# TMotor_Rev0.net
KiCad netlist of a schematic drawn in EAGLE
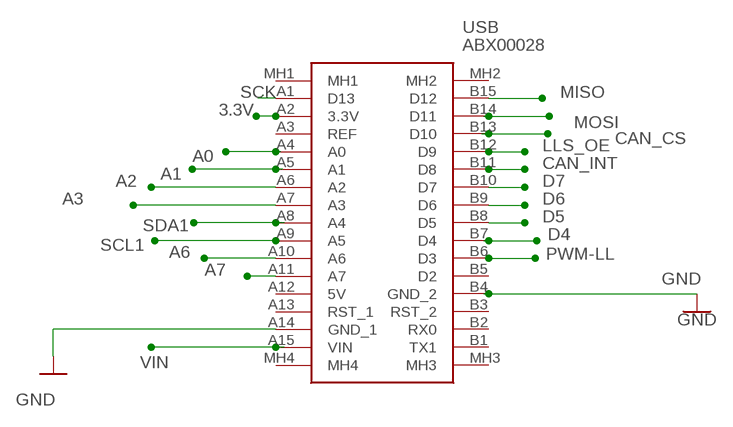
[diagram p0: schematic, sheet 1]
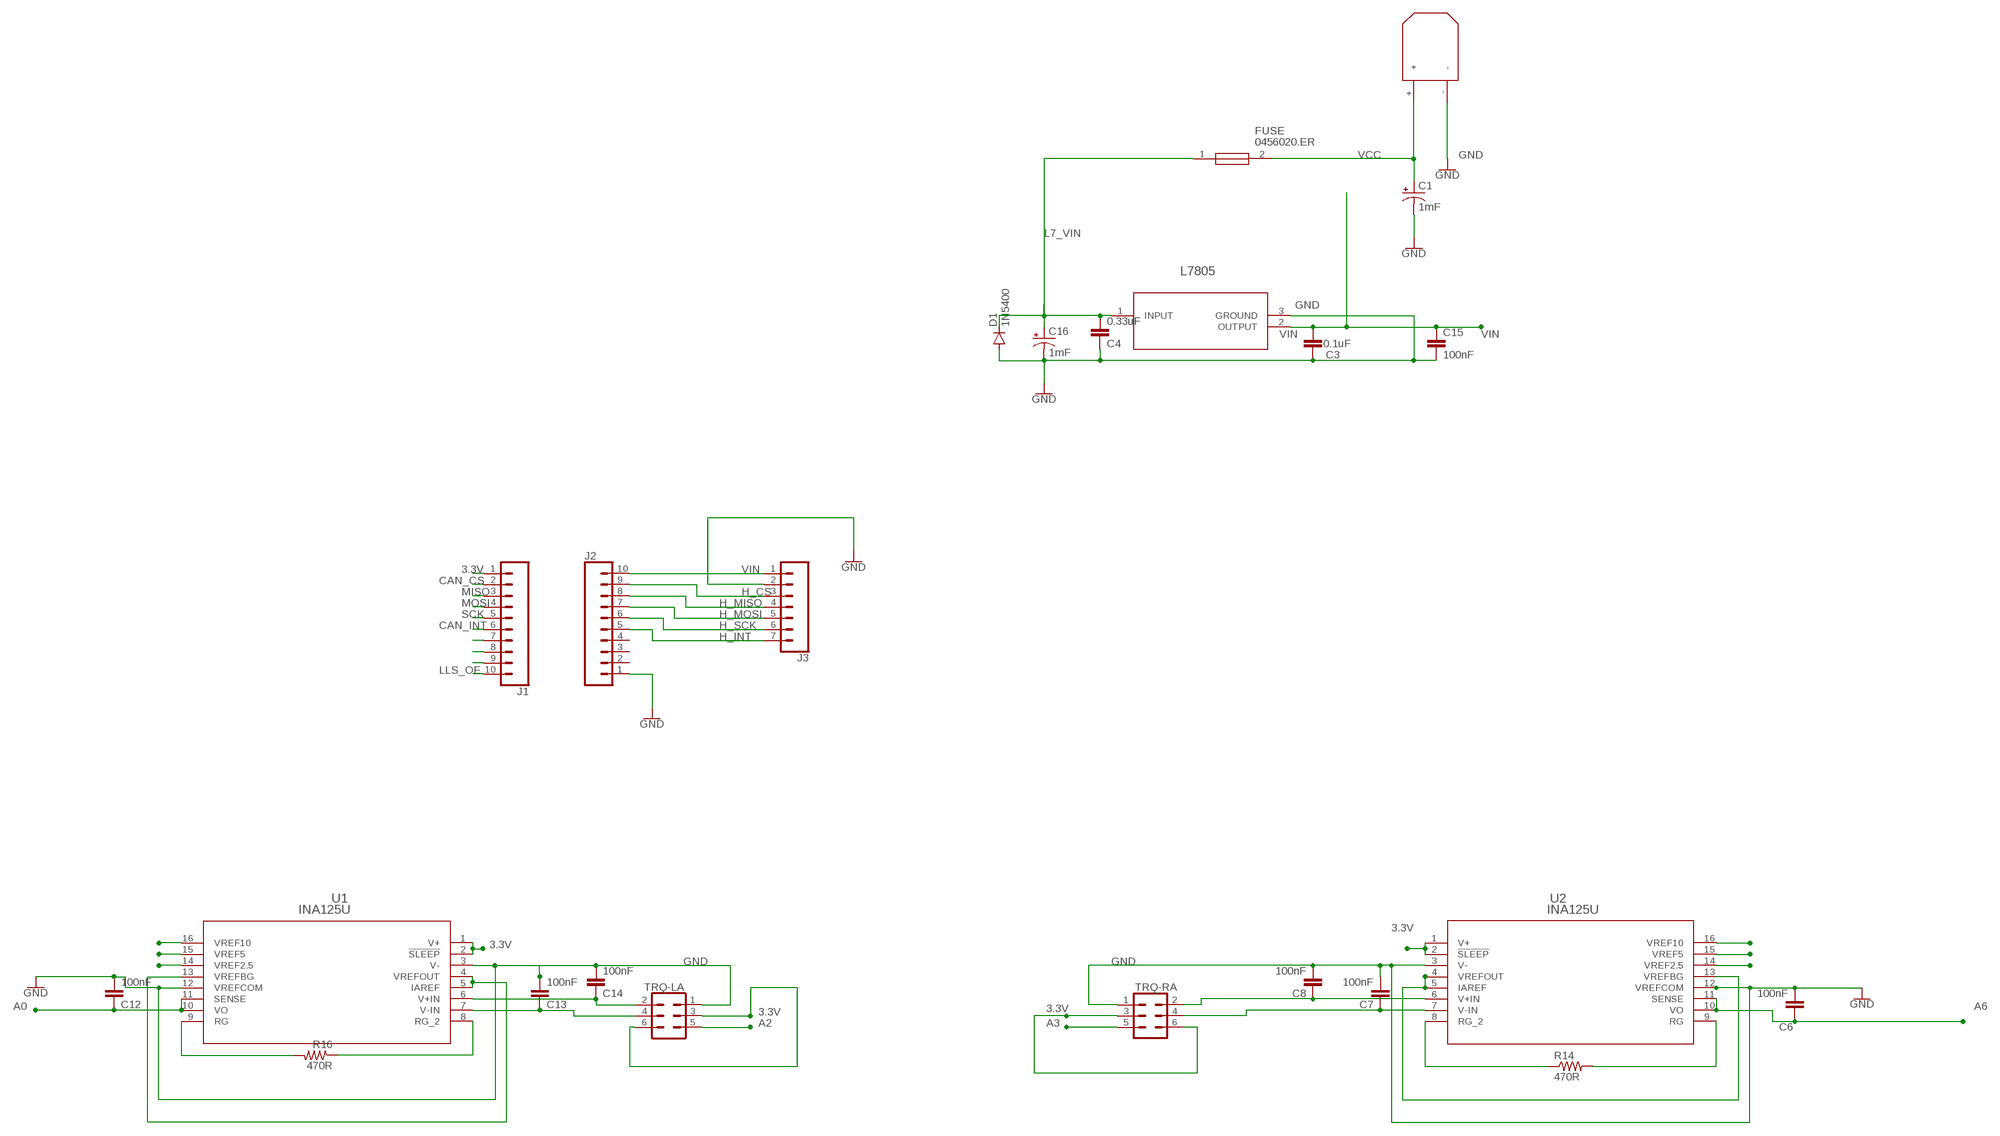
[diagram p1: schematic, sheet 2]
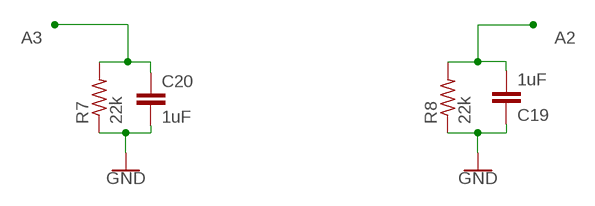
[diagram p2: schematic, sheet 3]

(export (version "E")
  (design (tool "Eeschema 10.0.6"))
  (components
    (comp (ref "C19")
      (value "1uF")
      (footprint "eagle-import:C050-024X044")
      (libsource (lib "eagle-import") (part "C-EU050-024X044"))
    )
    (comp (ref "C20")
      (value "1uF")
      (footprint "eagle-import:C050-024X044")
      (libsource (lib "eagle-import") (part "C-EU050-024X044"))
    )
    (comp (ref "R7")
      (value "22k")
      (footprint "eagle-import:0207_10")
      (libsource (lib "eagle-import") (part "resistor_348_R-US_0207/10"))
    )
    (comp (ref "R8")
      (value "22k")
      (footprint "eagle-import:0207_10")
      (libsource (lib "eagle-import") (part "resistor_348_R-US_0207/10"))
    )
    (comp (ref "C1")
      (value "1mF")
      (footprint "eagle-import:E5-10,5")
      (libsource (lib "eagle-import") (part "CPOL-USE5-10.5"))
    )
    (comp (ref "C3")
      (value "0.1uF")
      (footprint "eagle-import:C050-024X044")
      (libsource (lib "eagle-import") (part "C-EU050-024X044"))
    )
    (comp (ref "C4")
      (value "0.33uF")
      (footprint "eagle-import:C050-024X044")
      (libsource (lib "eagle-import") (part "C-EU050-024X044"))
    )
    (comp (ref "C6")
      (value "100nF")
      (footprint "eagle-import:C050-024X044")
      (libsource (lib "eagle-import") (part "C-EU050-024X044"))
    )
    (comp (ref "C7")
      (value "100nF")
      (footprint "eagle-import:C050-024X044")
      (libsource (lib "eagle-import") (part "C-EU050-024X044"))
    )
    (comp (ref "C8")
      (value "100nF")
      (footprint "eagle-import:C050-024X044")
      (libsource (lib "eagle-import") (part "C-EU050-024X044"))
    )
    (comp (ref "C12")
      (value "100nF")
      (footprint "eagle-import:C050-024X044")
      (libsource (lib "eagle-import") (part "C-EU050-024X044"))
    )
    (comp (ref "C13")
      (value "100nF")
      (footprint "eagle-import:C050-024X044")
      (libsource (lib "eagle-import") (part "C-EU050-024X044"))
    )
    (comp (ref "C14")
      (value "100nF")
      (footprint "eagle-import:C050-024X044")
      (libsource (lib "eagle-import") (part "C-EU050-024X044"))
    )
    (comp (ref "C15")
      (value "100nF")
      (footprint "eagle-import:C050-024X044")
      (libsource (lib "eagle-import") (part "C-EU050-024X044"))
    )
    (comp (ref "C16")
      (value "1mF")
      (footprint "eagle-import:E5-10,5")
      (libsource (lib "eagle-import") (part "CPOL-USE5-10.5"))
    )
    (comp (ref "D1")
      (value "1N5400")
      (footprint "eagle-import:DO201-15")
      (libsource (lib "eagle-import") (part "1N5400"))
    )
    (comp (ref "FUSE")
      (value "0456020.ER")
      (footprint "eagle-import:FUSC10131X312N")
      (fields (field (name "MOUSER_PART_NUMBER") "576-0456020.ER"))
      (libsource (lib "eagle-import") (part "0456020.ER"))
    )
    (comp (ref "J1")
      (value "CONN_10\"")
      (footprint "eagle-import:1X10")
      (libsource (lib "eagle-import") (part "CONN_10{dblquote}"))
    )
    (comp (ref "J2")
      (value "CONN_10\"")
      (footprint "eagle-import:1X10")
      (libsource (lib "eagle-import") (part "CONN_10{dblquote}"))
    )
    (comp (ref "J3")
      (value "CONN_07")
      (footprint "eagle-import:1X07")
      (libsource (lib "eagle-import") (part "CONN_07"))
    )
    (comp (ref "L7805")
      (value "L7805CDT-TR")
      (footprint "eagle-import:DPAK_STM")
      (libsource (lib "eagle-import") (part "L7805CDT-TR"))
    )
    (comp (ref "R14")
      (value "470R")
      (footprint "eagle-import:0207_10")
      (libsource (lib "eagle-import") (part "R-US_0207/10"))
    )
    (comp (ref "R16")
      (value "470R")
      (footprint "eagle-import:0207_10")
      (libsource (lib "eagle-import") (part "R-US_0207/10"))
    )
    (comp (ref "TRQ-LA")
      (value "CONN_03X2SHROUD")
      (footprint "eagle-import:2X3-SHROUDED")
      (libsource (lib "eagle-import") (part "CONN_03X2SHROUD"))
    )
    (comp (ref "TRQ-RA")
      (value "CONN_03X2SHROUD")
      (footprint "eagle-import:2X3-SHROUDED")
      (libsource (lib "eagle-import") (part "CONN_03X2SHROUD"))
    )
    (comp (ref "U$9")
      (value "XT30")
      (footprint "eagle-import:XT30_HORIZONTAL")
      (libsource (lib "eagle-import") (part "XT30"))
    )
    (comp (ref "U1")
      (value "INA125U")
      (footprint "eagle-import:D16")
      (fields (field (name "GENERIC_PART_NUMBER") "INA125") (field (name "MANUFACTURER") "Texas Instruments"))
      (libsource (lib "eagle-import") (part "INA125U"))
    )
    (comp (ref "U2")
      (value "INA125U")
      (footprint "eagle-import:D16")
      (fields (field (name "GENERIC_PART_NUMBER") "INA125") (field (name "MANUFACTURER") "Texas Instruments"))
      (libsource (lib "eagle-import") (part "INA125U"))
    )
    (comp (ref "USB")
      (value "ABX00028")
      (footprint "eagle-import:ABX00028")
      (fields (field (name "MOUSER_PART_NUMBER") "782-ABX00028"))
      (libsource (lib "eagle-import") (part "ABX00028"))
    )
  )
  (nets
    (net (code "1") (name "3.3V") (class "Default")
      (node (ref "J1") (pin "1") (pinfunction "1_1") (pintype "passive"))
      (node (ref "TRQ-LA") (pin "3") (pinfunction "3_3") (pintype "bidirectional"))
      (node (ref "TRQ-LA") (pin "6") (pinfunction "6_6") (pintype "bidirectional"))
      (node (ref "TRQ-RA") (pin "3") (pinfunction "3_3") (pintype "bidirectional"))
      (node (ref "TRQ-RA") (pin "6") (pinfunction "6_6") (pintype "bidirectional"))
      (node (ref "U1") (pin "1") (pinfunction "V+_1") (pintype "power_in"))
      (node (ref "U1") (pin "2") (pinfunction "~{SLEEP}_2") (pintype "passive"))
      (node (ref "U2") (pin "1") (pinfunction "V+_1") (pintype "power_in"))
      (node (ref "U2") (pin "2") (pinfunction "~{SLEEP}_2") (pintype "passive"))
      (node (ref "USB") (pin "A2") (pinfunction "3.3V_A2") (pintype "bidirectional"))
    )
    (net (code "2") (name "A0") (class "Default")
      (node (ref "C12") (pin "1") (pinfunction "1_1") (pintype "passive"))
      (node (ref "U1") (pin "10") (pinfunction "VO_10") (pintype "output"))
      (node (ref "U1") (pin "11") (pinfunction "SENSE_11") (pintype "passive"))
      (node (ref "USB") (pin "A4") (pinfunction "A0_A4") (pintype "bidirectional"))
    )
    (net (code "3") (name "A1") (class "Default")
      (node (ref "USB") (pin "A5") (pinfunction "A1_A5") (pintype "bidirectional"))
    )
    (net (code "4") (name "A2") (class "Default")
      (node (ref "C19") (pin "2") (pinfunction "2_2") (pintype "passive"))
      (node (ref "R8") (pin "2") (pinfunction "2_2") (pintype "passive"))
      (node (ref "TRQ-LA") (pin "5") (pinfunction "5_5") (pintype "bidirectional"))
      (node (ref "USB") (pin "A6") (pinfunction "A2_A6") (pintype "bidirectional"))
    )
    (net (code "5") (name "A3") (class "Default")
      (node (ref "C20") (pin "1") (pinfunction "1_1") (pintype "passive"))
      (node (ref "R7") (pin "2") (pinfunction "2_2") (pintype "passive"))
      (node (ref "TRQ-RA") (pin "5") (pinfunction "5_5") (pintype "bidirectional"))
      (node (ref "USB") (pin "A7") (pinfunction "A3_A7") (pintype "bidirectional"))
    )
    (net (code "6") (name "A6") (class "Default")
      (node (ref "C6") (pin "1") (pinfunction "1_1") (pintype "passive"))
      (node (ref "U2") (pin "10") (pinfunction "VO_10") (pintype "output"))
      (node (ref "U2") (pin "11") (pinfunction "SENSE_11") (pintype "passive"))
      (node (ref "USB") (pin "A10") (pinfunction "A6_A10") (pintype "bidirectional"))
    )
    (net (code "7") (name "A7") (class "Default")
      (node (ref "USB") (pin "A11") (pinfunction "A7_A11") (pintype "bidirectional"))
    )
    (net (code "8") (name "CAN_CS") (class "Default")
      (node (ref "J1") (pin "2") (pinfunction "2_2") (pintype "passive"))
      (node (ref "USB") (pin "B13") (pinfunction "D10_B13") (pintype "bidirectional"))
    )
    (net (code "9") (name "CAN_INT") (class "Default")
      (node (ref "J1") (pin "6") (pinfunction "6_6") (pintype "passive"))
      (node (ref "USB") (pin "B11") (pinfunction "D8_B11") (pintype "bidirectional"))
    )
    (net (code "10") (name "D4") (class "Default")
      (node (ref "USB") (pin "B7") (pinfunction "D4_B7") (pintype "bidirectional"))
    )
    (net (code "11") (name "D5") (class "Default")
      (node (ref "USB") (pin "B8") (pinfunction "D5_B8") (pintype "bidirectional"))
    )
    (net (code "12") (name "D6") (class "Default")
      (node (ref "USB") (pin "B9") (pinfunction "D6_B9") (pintype "bidirectional"))
    )
    (net (code "13") (name "D7") (class "Default")
      (node (ref "USB") (pin "B10") (pinfunction "D7_B10") (pintype "bidirectional"))
    )
    (net (code "14") (name "GND") (class "Default")
      (node (ref "C1") (pin "-") (pinfunction "-_-") (pintype "passive"))
      (node (ref "C12") (pin "2") (pinfunction "2_2") (pintype "passive"))
      (node (ref "C13") (pin "2") (pinfunction "2_2") (pintype "passive"))
      (node (ref "C14") (pin "2") (pinfunction "2_2") (pintype "passive"))
      (node (ref "C15") (pin "2") (pinfunction "2_2") (pintype "passive"))
      (node (ref "C16") (pin "-") (pinfunction "-_-") (pintype "passive"))
      (node (ref "C19") (pin "1") (pinfunction "1_1") (pintype "passive"))
      (node (ref "C20") (pin "2") (pinfunction "2_2") (pintype "passive"))
      (node (ref "C3") (pin "1") (pinfunction "1_1") (pintype "passive"))
      (node (ref "C4") (pin "1") (pinfunction "1_1") (pintype "passive"))
      (node (ref "C6") (pin "2") (pinfunction "2_2") (pintype "passive"))
      (node (ref "C7") (pin "2") (pinfunction "2_2") (pintype "passive"))
      (node (ref "C8") (pin "2") (pinfunction "2_2") (pintype "passive"))
      (node (ref "D1") (pin "A") (pinfunction "A_A") (pintype "passive"))
      (node (ref "J2") (pin "1") (pinfunction "1_1") (pintype "passive"))
      (node (ref "J3") (pin "2") (pinfunction "2_2") (pintype "passive"))
      (node (ref "L7805") (pin "3") (pinfunction "GROUND_3") (pintype "passive"))
      (node (ref "R7") (pin "1") (pinfunction "1_1") (pintype "passive"))
      (node (ref "R8") (pin "1") (pinfunction "1_1") (pintype "passive"))
      (node (ref "TRQ-LA") (pin "1") (pinfunction "1_1") (pintype "bidirectional"))
      (node (ref "TRQ-RA") (pin "1") (pinfunction "1_1") (pintype "bidirectional"))
      (node (ref "U$9") (pin "-") (pinfunction "-_-") (pintype "bidirectional"))
      (node (ref "U1") (pin "12") (pinfunction "VREFCOM_12") (pintype "power_in"))
      (node (ref "U1") (pin "3") (pinfunction "V-_3") (pintype "power_in"))
      (node (ref "U2") (pin "12") (pinfunction "VREFCOM_12") (pintype "power_in"))
      (node (ref "U2") (pin "3") (pinfunction "V-_3") (pintype "power_in"))
      (node (ref "USB") (pin "A14") (pinfunction "GND_1_A14") (pintype "bidirectional"))
      (node (ref "USB") (pin "B4") (pinfunction "GND_2_B4") (pintype "bidirectional"))
    )
    (net (code "15") (name "H_CS") (class "Default")
      (node (ref "J2") (pin "9") (pinfunction "9_9") (pintype "passive"))
      (node (ref "J3") (pin "3") (pinfunction "3_3") (pintype "passive"))
    )
    (net (code "16") (name "H_INT") (class "Default")
      (node (ref "J2") (pin "5") (pinfunction "5_5") (pintype "passive"))
      (node (ref "J3") (pin "7") (pinfunction "7_7") (pintype "passive"))
    )
    (net (code "17") (name "H_MISO") (class "Default")
      (node (ref "J2") (pin "8") (pinfunction "8_8") (pintype "passive"))
      (node (ref "J3") (pin "4") (pinfunction "4_4") (pintype "passive"))
    )
    (net (code "18") (name "H_MOSI") (class "Default")
      (node (ref "J2") (pin "7") (pinfunction "7_7") (pintype "passive"))
      (node (ref "J3") (pin "5") (pinfunction "5_5") (pintype "passive"))
    )
    (net (code "19") (name "H_SCK") (class "Default")
      (node (ref "J2") (pin "6") (pinfunction "6_6") (pintype "passive"))
      (node (ref "J3") (pin "6") (pinfunction "6_6") (pintype "passive"))
    )
    (net (code "20") (name "L7_VIN") (class "Default")
      (node (ref "C16") (pin "+") (pinfunction "+_+") (pintype "passive"))
      (node (ref "C4") (pin "2") (pinfunction "2_2") (pintype "passive"))
      (node (ref "D1") (pin "C") (pinfunction "C_C") (pintype "passive"))
      (node (ref "FUSE") (pin "1") (pinfunction "1_1") (pintype "bidirectional"))
      (node (ref "L7805") (pin "1") (pinfunction "INPUT_1") (pintype "input"))
    )
    (net (code "21") (name "LLS_OE") (class "Default")
      (node (ref "J1") (pin "10") (pinfunction "10_10") (pintype "passive"))
      (node (ref "USB") (pin "B12") (pinfunction "D9_B12") (pintype "bidirectional"))
    )
    (net (code "22") (name "MISO") (class "Default")
      (node (ref "J1") (pin "3") (pinfunction "3_3") (pintype "passive"))
      (node (ref "USB") (pin "B15") (pinfunction "D12_B15") (pintype "bidirectional"))
    )
    (net (code "23") (name "MOSI") (class "Default")
      (node (ref "J1") (pin "4") (pinfunction "4_4") (pintype "passive"))
      (node (ref "USB") (pin "B14") (pinfunction "D11_B14") (pintype "bidirectional"))
    )
    (net (code "24") (name "Net-(U1-IAREF)") (class "Default")
      (node (ref "U1") (pin "13") (pinfunction "VREFBG_13") (pintype "power_in"))
      (node (ref "U1") (pin "4") (pinfunction "VREFOUT_4") (pintype "output"))
      (node (ref "U1") (pin "5") (pinfunction "IAREF_5") (pintype "passive"))
    )
    (net (code "25") (name "Net-(U1-RG)") (class "Default")
      (node (ref "R16") (pin "2") (pinfunction "2_2") (pintype "passive"))
      (node (ref "U1") (pin "9") (pinfunction "RG_9") (pintype "passive"))
    )
    (net (code "26") (name "Net-(U1-RG_2)") (class "Default")
      (node (ref "R16") (pin "1") (pinfunction "1_1") (pintype "passive"))
      (node (ref "U1") (pin "8") (pinfunction "RG_2_8") (pintype "passive"))
    )
    (net (code "27") (name "Net-(U1-V+IN)") (class "Default")
      (node (ref "C14") (pin "1") (pinfunction "1_1") (pintype "passive"))
      (node (ref "TRQ-LA") (pin "2") (pinfunction "2_2") (pintype "bidirectional"))
      (node (ref "U1") (pin "6") (pinfunction "V+IN_6") (pintype "input"))
    )
    (net (code "28") (name "Net-(U1-V-IN)") (class "Default")
      (node (ref "C13") (pin "1") (pinfunction "1_1") (pintype "passive"))
      (node (ref "TRQ-LA") (pin "4") (pinfunction "4_4") (pintype "bidirectional"))
      (node (ref "U1") (pin "7") (pinfunction "V-IN_7") (pintype "input"))
    )
    (net (code "29") (name "Net-(U2-IAREF)") (class "Default")
      (node (ref "U2") (pin "13") (pinfunction "VREFBG_13") (pintype "power_in"))
      (node (ref "U2") (pin "4") (pinfunction "VREFOUT_4") (pintype "output"))
      (node (ref "U2") (pin "5") (pinfunction "IAREF_5") (pintype "passive"))
    )
    (net (code "30") (name "Net-(U2-RG)") (class "Default")
      (node (ref "R14") (pin "2") (pinfunction "2_2") (pintype "passive"))
      (node (ref "U2") (pin "9") (pinfunction "RG_9") (pintype "passive"))
    )
    (net (code "31") (name "Net-(U2-RG_2)") (class "Default")
      (node (ref "R14") (pin "1") (pinfunction "1_1") (pintype "passive"))
      (node (ref "U2") (pin "8") (pinfunction "RG_2_8") (pintype "passive"))
    )
    (net (code "32") (name "Net-(U2-V+IN)") (class "Default")
      (node (ref "C8") (pin "1") (pinfunction "1_1") (pintype "passive"))
      (node (ref "TRQ-RA") (pin "2") (pinfunction "2_2") (pintype "bidirectional"))
      (node (ref "U2") (pin "6") (pinfunction "V+IN_6") (pintype "input"))
    )
    (net (code "33") (name "Net-(U2-V-IN)") (class "Default")
      (node (ref "C7") (pin "1") (pinfunction "1_1") (pintype "passive"))
      (node (ref "TRQ-RA") (pin "4") (pinfunction "4_4") (pintype "bidirectional"))
      (node (ref "U2") (pin "7") (pinfunction "V-IN_7") (pintype "input"))
    )
    (net (code "34") (name "PWM-LL") (class "Default")
      (node (ref "USB") (pin "B6") (pinfunction "D3_B6") (pintype "bidirectional"))
    )
    (net (code "35") (name "SCK") (class "Default")
      (node (ref "J1") (pin "5") (pinfunction "5_5") (pintype "passive"))
      (node (ref "USB") (pin "A1") (pinfunction "D13_A1") (pintype "bidirectional"))
    )
    (net (code "36") (name "SCL1") (class "Default")
      (node (ref "USB") (pin "A9") (pinfunction "A5_A9") (pintype "bidirectional"))
    )
    (net (code "37") (name "SDA1") (class "Default")
      (node (ref "USB") (pin "A8") (pinfunction "A4_A8") (pintype "bidirectional"))
    )
    (net (code "38") (name "VCC") (class "Default")
      (node (ref "C1") (pin "+") (pinfunction "+_+") (pintype "passive"))
      (node (ref "FUSE") (pin "2") (pinfunction "2_2") (pintype "bidirectional"))
      (node (ref "U$9") (pin "+") (pinfunction "+_+") (pintype "bidirectional"))
    )
    (net (code "39") (name "VIN") (class "Default")
      (node (ref "C15") (pin "1") (pinfunction "1_1") (pintype "passive"))
      (node (ref "C3") (pin "2") (pinfunction "2_2") (pintype "passive"))
      (node (ref "J2") (pin "10") (pinfunction "10_10") (pintype "passive"))
      (node (ref "J3") (pin "1") (pinfunction "1_1") (pintype "passive"))
      (node (ref "L7805") (pin "2") (pinfunction "OUTPUT_2") (pintype "output"))
      (node (ref "USB") (pin "A15") (pinfunction "VIN_A15") (pintype "bidirectional"))
    )
    (net (code "40") (name "unconnected-(J1-Pad7)") (class "Default")
      (node (ref "J1") (pin "7") (pinfunction "7_7") (pintype "passive"))
    )
    (net (code "41") (name "unconnected-(J1-Pad8)") (class "Default")
      (node (ref "J1") (pin "8") (pinfunction "8_8") (pintype "passive"))
    )
    (net (code "42") (name "unconnected-(J1-Pad9)") (class "Default")
      (node (ref "J1") (pin "9") (pinfunction "9_9") (pintype "passive"))
    )
    (net (code "43") (name "unconnected-(J2-Pad2)") (class "Default")
      (node (ref "J2") (pin "2") (pinfunction "2_2") (pintype "passive"))
    )
    (net (code "44") (name "unconnected-(J2-Pad3)") (class "Default")
      (node (ref "J2") (pin "3") (pinfunction "3_3") (pintype "passive"))
    )
    (net (code "45") (name "unconnected-(J2-Pad4)") (class "Default")
      (node (ref "J2") (pin "4") (pinfunction "4_4") (pintype "passive"))
    )
    (net (code "46") (name "unconnected-(U1-VREF2.5-Pad14)") (class "Default")
      (node (ref "U1") (pin "14") (pinfunction "VREF2.5_14") (pintype "power_in"))
    )
    (net (code "47") (name "unconnected-(U1-VREF5-Pad15)") (class "Default")
      (node (ref "U1") (pin "15") (pinfunction "VREF5_15") (pintype "power_in"))
    )
    (net (code "48") (name "unconnected-(U1-VREF10-Pad16)") (class "Default")
      (node (ref "U1") (pin "16") (pinfunction "VREF10_16") (pintype "power_in"))
    )
    (net (code "49") (name "unconnected-(U2-VREF2.5-Pad14)") (class "Default")
      (node (ref "U2") (pin "14") (pinfunction "VREF2.5_14") (pintype "power_in"))
    )
    (net (code "50") (name "unconnected-(U2-VREF5-Pad15)") (class "Default")
      (node (ref "U2") (pin "15") (pinfunction "VREF5_15") (pintype "power_in"))
    )
    (net (code "51") (name "unconnected-(U2-VREF10-Pad16)") (class "Default")
      (node (ref "U2") (pin "16") (pinfunction "VREF10_16") (pintype "power_in"))
    )
    (net (code "52") (name "unconnected-(USB-5V-PadA12)") (class "Default")
      (node (ref "USB") (pin "A12") (pinfunction "5V_A12") (pintype "bidirectional"))
    )
    (net (code "53") (name "unconnected-(USB-D2-PadB5)") (class "Default")
      (node (ref "USB") (pin "B5") (pinfunction "D2_B5") (pintype "bidirectional"))
    )
    (net (code "54") (name "unconnected-(USB-PadMH1)") (class "Default")
      (node (ref "USB") (pin "MH1") (pinfunction "MH1_MH1") (pintype "bidirectional"))
    )
    (net (code "55") (name "unconnected-(USB-PadMH2)") (class "Default")
      (node (ref "USB") (pin "MH2") (pinfunction "MH2_MH2") (pintype "bidirectional"))
    )
    (net (code "56") (name "unconnected-(USB-PadMH3)") (class "Default")
      (node (ref "USB") (pin "MH3") (pinfunction "MH3_MH3") (pintype "bidirectional"))
    )
    (net (code "57") (name "unconnected-(USB-PadMH4)") (class "Default")
      (node (ref "USB") (pin "MH4") (pinfunction "MH4_MH4") (pintype "bidirectional"))
    )
    (net (code "58") (name "unconnected-(USB-REF-PadA3)") (class "Default")
      (node (ref "USB") (pin "A3") (pinfunction "REF_A3") (pintype "bidirectional"))
    )
    (net (code "59") (name "unconnected-(USB-RST_1-PadA13)") (class "Default")
      (node (ref "USB") (pin "A13") (pinfunction "RST_1_A13") (pintype "bidirectional"))
    )
    (net (code "60") (name "unconnected-(USB-RST_2-PadB3)") (class "Default")
      (node (ref "USB") (pin "B3") (pinfunction "RST_2_B3") (pintype "bidirectional"))
    )
    (net (code "61") (name "unconnected-(USB-RX0-PadB2)") (class "Default")
      (node (ref "USB") (pin "B2") (pinfunction "RX0_B2") (pintype "bidirectional"))
    )
    (net (code "62") (name "unconnected-(USB-TX1-PadB1)") (class "Default")
      (node (ref "USB") (pin "B1") (pinfunction "TX1_B1") (pintype "bidirectional"))
    )
  )
)
